# Pixel.net
KiCad netlist of a schematic drawn in EAGLE
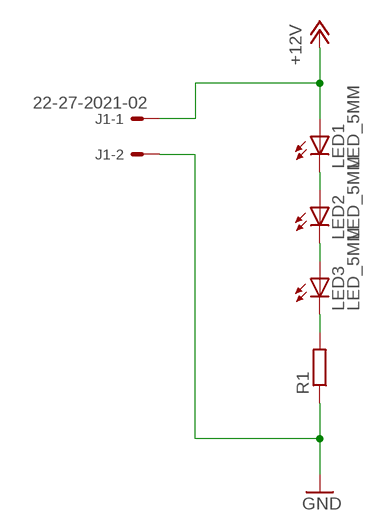
[diagram p0: schematic, sheet 1]

(export (version "E")
  (design (tool "Eeschema 10.0.6"))
  (components
    (comp (ref "J1")
      (value "22-27-2021-02")
      (footprint "eagle-import:6410-02")
      (libsource (lib "eagle-import") (part "22-?-0227-2021"))
    )
    (comp (ref "LED1")
      (value "LED_5MM")
      (footprint "eagle-import:LED_5MM")
      (libsource (lib "eagle-import") (part "LED_5MM"))
    )
    (comp (ref "LED2")
      (value "LED_5MM")
      (footprint "eagle-import:LED_5MM")
      (libsource (lib "eagle-import") (part "LED_5MM"))
    )
    (comp (ref "LED3")
      (value "LED_5MM")
      (footprint "eagle-import:LED_5MM")
      (libsource (lib "eagle-import") (part "LED_5MM"))
    )
    (comp (ref "R1")
      (value "RESISTOR-1/4W-SMD-1206")
      (footprint "eagle-import:R1206")
      (libsource (lib "eagle-import") (part "RESISTOR-1/4W-SMD-1206"))
    )
  )
  (nets
    (net (code "1") (name "+12V") (class "Default")
      (node (ref "J1") (pin "1") (pinfunction "S_1") (pintype "passive"))
      (node (ref "LED1") (pin "ANODE") (pinfunction "ANODE_ANODE") (pintype "passive"))
    )
    (net (code "2") (name "GND") (class "Default")
      (node (ref "J1") (pin "2") (pinfunction "S_2") (pintype "passive"))
      (node (ref "R1") (pin "P$1") (pinfunction "1_P$1") (pintype "passive"))
    )
    (net (code "3") (name "Net-(LED1-PadCATHODE)") (class "Default")
      (node (ref "LED1") (pin "CATHODE") (pinfunction "CATHODE_CATHODE") (pintype "passive"))
      (node (ref "LED2") (pin "ANODE") (pinfunction "ANODE_ANODE") (pintype "passive"))
    )
    (net (code "4") (name "Net-(LED2-PadCATHODE)") (class "Default")
      (node (ref "LED2") (pin "CATHODE") (pinfunction "CATHODE_CATHODE") (pintype "passive"))
      (node (ref "LED3") (pin "ANODE") (pinfunction "ANODE_ANODE") (pintype "passive"))
    )
    (net (code "5") (name "Net-(R1-2)") (class "Default")
      (node (ref "LED3") (pin "CATHODE") (pinfunction "CATHODE_CATHODE") (pintype "passive"))
      (node (ref "R1") (pin "P$2") (pinfunction "2_P$2") (pintype "passive"))
    )
  )
)
